# room_sensor.net
KiCad netlist of a schematic drawn in EAGLE
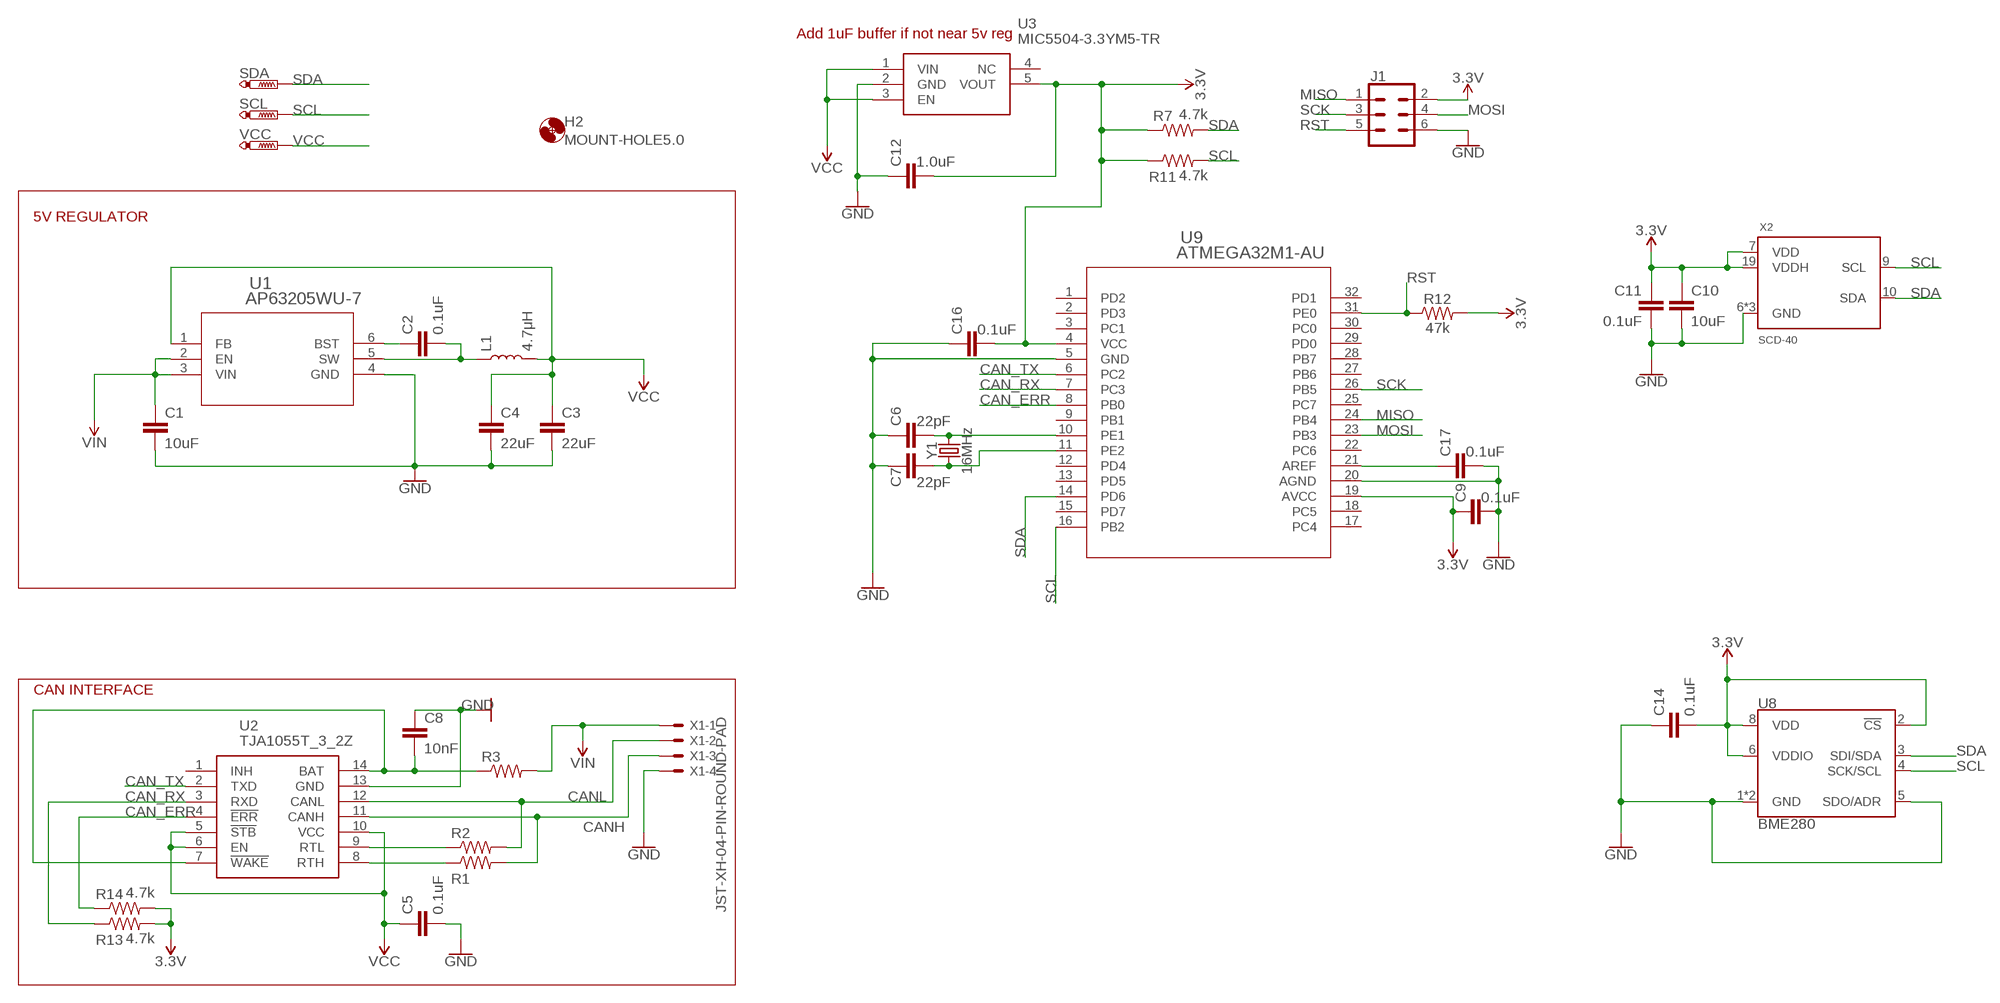
[diagram p0: schematic, sheet 1]

(export (version "E")
  (design (tool "Eeschema 10.0.6"))
  (components
    (comp (ref "C1")
      (value "10uF")
      (footprint "eagle-import:1210")
      (libsource (lib "eagle-import") (part "10UF-1210-50V-20%"))
    )
    (comp (ref "C2")
      (value "0.1uF")
      (footprint "eagle-import:0603")
      (libsource (lib "eagle-import") (part "0.1UF-0603-25V-5%"))
    )
    (comp (ref "C3")
      (value "22uF")
      (footprint "eagle-import:0805")
      (libsource (lib "eagle-import") (part "22UF-0805-6.3V-20%"))
    )
    (comp (ref "C4")
      (value "22uF")
      (footprint "eagle-import:0805")
      (libsource (lib "eagle-import") (part "22UF-0805-6.3V-20%"))
    )
    (comp (ref "C5")
      (value "0.1uF")
      (footprint "eagle-import:0603")
      (libsource (lib "eagle-import") (part "0.1UF-0603-25V-5%"))
    )
    (comp (ref "C6")
      (value "22pF")
      (footprint "eagle-import:0603")
      (libsource (lib "eagle-import") (part "22PF-0603-50V-5%"))
    )
    (comp (ref "C7")
      (value "22pF")
      (footprint "eagle-import:0603")
      (libsource (lib "eagle-import") (part "22PF-0603-50V-5%"))
    )
    (comp (ref "C8")
      (value "10nF")
      (footprint "eagle-import:0603")
      (libsource (lib "eagle-import") (part "10NF-0603-50V-10%"))
    )
    (comp (ref "C9")
      (value "0.1uF")
      (footprint "eagle-import:0603")
      (libsource (lib "eagle-import") (part "0.1UF-0603-25V-5%"))
    )
    (comp (ref "C10")
      (value "10uF")
      (footprint "eagle-import:1210")
      (libsource (lib "eagle-import") (part "10UF-1210-50V-20%"))
    )
    (comp (ref "C11")
      (value "0.1uF")
      (footprint "eagle-import:0603")
      (libsource (lib "eagle-import") (part "0.1UF-0603-25V-5%"))
    )
    (comp (ref "C12")
      (value "1.0uF")
      (footprint "eagle-import:0603")
      (libsource (lib "eagle-import") (part "1.0UF-0603-16V-10%"))
    )
    (comp (ref "C14")
      (value "0.1uF")
      (footprint "eagle-import:0603")
      (libsource (lib "eagle-import") (part "0.1UF-0603-25V-5%"))
    )
    (comp (ref "C16")
      (value "0.1uF")
      (footprint "eagle-import:0603")
      (libsource (lib "eagle-import") (part "0.1UF-0603-25V-5%"))
    )
    (comp (ref "C17")
      (value "0.1uF")
      (footprint "eagle-import:0603")
      (libsource (lib "eagle-import") (part "0.1UF-0603-25V-5%"))
    )
    (comp (ref "H2")
      (value "MOUNT-HOLE5.0")
      (footprint "eagle-import:5,0")
      (libsource (lib "eagle-import") (part "MOUNT-HOLE5.0"))
    )
    (comp (ref "J1")
      (value "CONN_03X2NO_SILK")
      (footprint "eagle-import:2X3-NS")
      (libsource (lib "eagle-import") (part "CONN_03X2NO_SILK"))
    )
    (comp (ref "L1")
      (value "4.7μH")
      (footprint "eagle-import:INDUCTOR_4X4MM")
      (libsource (lib "eagle-import") (part "4.7μH_SHIELDED_INDUCTORNPIS_LS"))
    )
    (comp (ref "R1")
      (value "RESISTOR0603")
      (footprint "eagle-import:0603")
      (libsource (lib "eagle-import") (part "RESISTOR0603"))
    )
    (comp (ref "R2")
      (value "RESISTOR0603")
      (footprint "eagle-import:0603")
      (libsource (lib "eagle-import") (part "RESISTOR0603"))
    )
    (comp (ref "R3")
      (value "RESISTOR0603")
      (footprint "eagle-import:0603")
      (libsource (lib "eagle-import") (part "RESISTOR0603"))
    )
    (comp (ref "R7")
      (value "4.7k")
      (footprint "eagle-import:0603")
      (libsource (lib "eagle-import") (part "4.7KOHM-0603-1/10W-1%"))
    )
    (comp (ref "R11")
      (value "4.7k")
      (footprint "eagle-import:0603")
      (libsource (lib "eagle-import") (part "4.7KOHM-0603-1/10W-1%"))
    )
    (comp (ref "R12")
      (value "47k")
      (footprint "eagle-import:0603")
      (libsource (lib "eagle-import") (part "47KOHM-0603-1/10W-1%"))
    )
    (comp (ref "R13")
      (value "4.7k")
      (footprint "eagle-import:0603")
      (libsource (lib "eagle-import") (part "4.7KOHM-0603-1/10W-1%"))
    )
    (comp (ref "R14")
      (value "4.7k")
      (footprint "eagle-import:0603")
      (libsource (lib "eagle-import") (part "4.7KOHM-0603-1/10W-1%"))
    )
    (comp (ref "SCL")
      (value "PTR1B1,27")
      (footprint "eagle-import:B1,27")
      (libsource (lib "eagle-import") (part "PTR1B1,27"))
    )
    (comp (ref "SDA")
      (value "PTR1B1,27")
      (footprint "eagle-import:B1,27")
      (libsource (lib "eagle-import") (part "PTR1B1,27"))
    )
    (comp (ref "U1")
      (value "AP63205WU-7")
      (footprint "eagle-import:SOIC_05WU-7_DIO")
      (fields (field (name "COPYRIGHT") "Copyright (C) 2023 Ultra Librarian. All rights reserved."))
      (libsource (lib "eagle-import") (part "AP63205WU-7"))
    )
    (comp (ref "U2")
      (value "TJA1055T_3_2Z")
      (footprint "eagle-import:SOIC127P600X175-14N")
      (fields
        (field (name "MANUFACTURER_PART_NUMBER") "TJA1055T/3/2Z")
        (field (name "MOUSER_PART_NUMBER") "771-TJA1055T/3/2Z")
      )
      (libsource (lib "eagle-import") (part "TJA1055T_3_2Z"))
    )
    (comp (ref "U3")
      (value "MIC5504-3.3YM5-TR")
      (footprint "eagle-import:SOT95P280X145-5N")
      (fields (field (name "MOUSER_PART_NUMBER") "998-MIC5504-3.3YM5TR"))
      (libsource (lib "eagle-import") (part "MIC5504-3.3YM5-TR"))
    )
    (comp (ref "U8")
      (value "BME280")
      (footprint "eagle-import:LGA-8-2.5X2.5")
      (libsource (lib "eagle-import") (part "BME280"))
    )
    (comp (ref "U9")
      (value "ATMEGA32M1-AU")
      (footprint "eagle-import:32A_ATM")
      (fields (field (name "COPYRIGHT") "Copyright (C) 2023 Ultra Librarian. All rights reserved."))
      (libsource (lib "eagle-import") (part "ATMEGA32M1-AU"))
    )
    (comp (ref "VCC")
      (value "PTR1B1,27")
      (footprint "eagle-import:B1,27")
      (libsource (lib "eagle-import") (part "PTR1B1,27"))
    )
    (comp (ref "X1")
      (value "JST-XH-04-PIN-ROUND-PAD")
      (footprint "eagle-import:JST-XH-04-PACKAGE-ROUND-PAD")
      (libsource (lib "eagle-import") (part "JST-XH-04-PIN-ROUND-PAD"))
    )
    (comp (ref "X2")
      (value "SCD-40")
      (footprint "eagle-import:SCD40")
      (libsource (lib "eagle-import") (part "SCD-40"))
    )
    (comp (ref "Y1")
      (value "16MHz")
      (footprint "eagle-import:CRYSTAL-SMD-5X3.2-4PAD")
      (libsource (lib "eagle-import") (part "CRYSTAL-16MHZSMD-5X3.2"))
    )
  )
  (nets
    (net (code "1") (name "/CANH") (class "Default")
      (node (ref "R1") (pin "2") (pinfunction "2_2") (pintype "passive"))
      (node (ref "U2") (pin "11") (pinfunction "CANH_11") (pintype "bidirectional"))
      (node (ref "X1") (pin "3") (pinfunction "S_3") (pintype "passive"))
    )
    (net (code "2") (name "/CANL") (class "Default")
      (node (ref "R2") (pin "2") (pinfunction "2_2") (pintype "passive"))
      (node (ref "U2") (pin "12") (pinfunction "CANL_12") (pintype "bidirectional"))
      (node (ref "X1") (pin "2") (pinfunction "S_2") (pintype "passive"))
    )
    (net (code "3") (name "/CAN_ERR") (class "Default")
      (node (ref "R14") (pin "1") (pinfunction "1_1") (pintype "passive"))
      (node (ref "U2") (pin "4") (pinfunction "~{ERR}_4") (pintype "bidirectional"))
      (node (ref "U9") (pin "8") (pinfunction "PB0_8") (pintype "bidirectional"))
    )
    (net (code "4") (name "/CAN_RX") (class "Default")
      (node (ref "R13") (pin "1") (pinfunction "1_1") (pintype "passive"))
      (node (ref "U2") (pin "3") (pinfunction "RXD_3") (pintype "bidirectional"))
      (node (ref "U9") (pin "7") (pinfunction "PC3_7") (pintype "bidirectional"))
    )
    (net (code "5") (name "/CAN_TX") (class "Default")
      (node (ref "U2") (pin "2") (pinfunction "TXD_2") (pintype "bidirectional"))
      (node (ref "U9") (pin "6") (pinfunction "PC2_6") (pintype "bidirectional"))
    )
    (net (code "6") (name "/MISO") (class "Default")
      (node (ref "J1") (pin "1") (pinfunction "1_1") (pintype "bidirectional"))
      (node (ref "U9") (pin "24") (pinfunction "PB4_24") (pintype "bidirectional"))
    )
    (net (code "7") (name "/MOSI") (class "Default")
      (node (ref "J1") (pin "4") (pinfunction "4_4") (pintype "bidirectional"))
      (node (ref "U9") (pin "23") (pinfunction "PB3_23") (pintype "bidirectional"))
    )
    (net (code "8") (name "/RST") (class "Default")
      (node (ref "J1") (pin "5") (pinfunction "5_5") (pintype "bidirectional"))
      (node (ref "R12") (pin "1") (pinfunction "1_1") (pintype "passive"))
      (node (ref "U9") (pin "31") (pinfunction "PE0_31") (pintype "bidirectional"))
    )
    (net (code "9") (name "/SCK") (class "Default")
      (node (ref "J1") (pin "3") (pinfunction "3_3") (pintype "bidirectional"))
      (node (ref "U9") (pin "26") (pinfunction "PB5_26") (pintype "bidirectional"))
    )
    (net (code "10") (name "/SCL") (class "Default")
      (node (ref "R11") (pin "2") (pinfunction "2_2") (pintype "passive"))
      (node (ref "SCL") (pin "TP") (pinfunction "TP_TP") (pintype "input"))
      (node (ref "U8") (pin "4") (pinfunction "SCK/SCL_4") (pintype "bidirectional"))
      (node (ref "U9") (pin "16") (pinfunction "PB2_16") (pintype "bidirectional"))
      (node (ref "X2") (pin "9") (pinfunction "SCL_9") (pintype "input"))
    )
    (net (code "11") (name "/SDA") (class "Default")
      (node (ref "R7") (pin "2") (pinfunction "2_2") (pintype "passive"))
      (node (ref "SDA") (pin "TP") (pinfunction "TP_TP") (pintype "input"))
      (node (ref "U8") (pin "3") (pinfunction "SDI/SDA_3") (pintype "bidirectional"))
      (node (ref "U9") (pin "14") (pinfunction "PD6_14") (pintype "bidirectional"))
      (node (ref "X2") (pin "10") (pinfunction "SDA_10") (pintype "bidirectional"))
    )
    (net (code "12") (name "3.3V") (class "Default")
      (node (ref "C10") (pin "1") (pinfunction "1_1") (pintype "passive"))
      (node (ref "C11") (pin "2") (pinfunction "2_2") (pintype "passive"))
      (node (ref "C12") (pin "2") (pinfunction "2_2") (pintype "passive"))
      (node (ref "C14") (pin "2") (pinfunction "2_2") (pintype "passive"))
      (node (ref "C16") (pin "2") (pinfunction "2_2") (pintype "passive"))
      (node (ref "C9") (pin "1") (pinfunction "1_1") (pintype "passive"))
      (node (ref "J1") (pin "2") (pinfunction "2_2") (pintype "bidirectional"))
      (node (ref "R11") (pin "1") (pinfunction "1_1") (pintype "passive"))
      (node (ref "R12") (pin "2") (pinfunction "2_2") (pintype "passive"))
      (node (ref "R13") (pin "2") (pinfunction "2_2") (pintype "passive"))
      (node (ref "R14") (pin "2") (pinfunction "2_2") (pintype "passive"))
      (node (ref "R7") (pin "1") (pinfunction "1_1") (pintype "passive"))
      (node (ref "U3") (pin "5") (pinfunction "VOUT_5") (pintype "bidirectional"))
      (node (ref "U8") (pin "2") (pinfunction "~{CS}_2") (pintype "bidirectional"))
      (node (ref "U8") (pin "6") (pinfunction "VDDIO_6") (pintype "bidirectional"))
      (node (ref "U8") (pin "8") (pinfunction "VDD_8") (pintype "bidirectional"))
      (node (ref "U9") (pin "19") (pinfunction "AVCC_19") (pintype "power_in"))
      (node (ref "U9") (pin "4") (pinfunction "VCC_4") (pintype "power_in"))
      (node (ref "X2") (pin "19") (pinfunction "VDDH_19") (pintype "power_in"))
      (node (ref "X2") (pin "7") (pinfunction "VDD_7") (pintype "power_in"))
    )
    (net (code "13") (name "GND") (class "Default")
      (node (ref "C1") (pin "2") (pinfunction "2_2") (pintype "passive"))
      (node (ref "C10") (pin "2") (pinfunction "2_2") (pintype "passive"))
      (node (ref "C11") (pin "1") (pinfunction "1_1") (pintype "passive"))
      (node (ref "C12") (pin "1") (pinfunction "1_1") (pintype "passive"))
      (node (ref "C14") (pin "1") (pinfunction "1_1") (pintype "passive"))
      (node (ref "C16") (pin "1") (pinfunction "1_1") (pintype "passive"))
      (node (ref "C17") (pin "2") (pinfunction "2_2") (pintype "passive"))
      (node (ref "C3") (pin "2") (pinfunction "2_2") (pintype "passive"))
      (node (ref "C4") (pin "2") (pinfunction "2_2") (pintype "passive"))
      (node (ref "C5") (pin "2") (pinfunction "2_2") (pintype "passive"))
      (node (ref "C6") (pin "1") (pinfunction "1_1") (pintype "passive"))
      (node (ref "C7") (pin "1") (pinfunction "1_1") (pintype "passive"))
      (node (ref "C8") (pin "1") (pinfunction "1_1") (pintype "passive"))
      (node (ref "C9") (pin "2") (pinfunction "2_2") (pintype "passive"))
      (node (ref "J1") (pin "6") (pinfunction "6_6") (pintype "bidirectional"))
      (node (ref "U1") (pin "4") (pinfunction "GND_4") (pintype "passive"))
      (node (ref "U2") (pin "13") (pinfunction "GND_13") (pintype "bidirectional"))
      (node (ref "U3") (pin "2") (pinfunction "GND_2") (pintype "bidirectional"))
      (node (ref "U8") (pin "1") (pinfunction "GND_1") (pintype "bidirectional"))
      (node (ref "U8") (pin "5") (pinfunction "SDO/ADR_5") (pintype "bidirectional"))
      (node (ref "U8") (pin "7") (pinfunction "GND_7") (pintype "bidirectional"))
      (node (ref "U9") (pin "20") (pinfunction "AGND_20") (pintype "power_in"))
      (node (ref "U9") (pin "5") (pinfunction "GND_5") (pintype "power_in"))
      (node (ref "X1") (pin "4") (pinfunction "S_4") (pintype "passive"))
      (node (ref "X2") (pin "20") (pinfunction "GND_20") (pintype "power_in"))
      (node (ref "X2") (pin "6") (pinfunction "GND_6") (pintype "power_in"))
      (node (ref "X2") (pin "P$1") (pinfunction "GND_P$1") (pintype "power_in"))
    )
    (net (code "14") (name "Net-(L1-1)") (class "Default")
      (node (ref "C2") (pin "2") (pinfunction "2_2") (pintype "passive"))
      (node (ref "L1") (pin "P$1") (pinfunction "1_P$1") (pintype "passive"))
      (node (ref "U1") (pin "5") (pinfunction "SW_5") (pintype "passive"))
    )
    (net (code "15") (name "Net-(U1-BST)") (class "Default")
      (node (ref "C2") (pin "1") (pinfunction "1_1") (pintype "passive"))
      (node (ref "U1") (pin "6") (pinfunction "BST_6") (pintype "passive"))
    )
    (net (code "16") (name "Net-(U2-BAT)") (class "Default")
      (node (ref "C8") (pin "2") (pinfunction "2_2") (pintype "passive"))
      (node (ref "R3") (pin "1") (pinfunction "1_1") (pintype "passive"))
      (node (ref "U2") (pin "14") (pinfunction "BAT_14") (pintype "bidirectional"))
      (node (ref "U2") (pin "7") (pinfunction "~{WAKE}_7") (pintype "bidirectional"))
    )
    (net (code "17") (name "Net-(U2-RTH)") (class "Default")
      (node (ref "R1") (pin "1") (pinfunction "1_1") (pintype "passive"))
      (node (ref "U2") (pin "8") (pinfunction "RTH_8") (pintype "bidirectional"))
    )
    (net (code "18") (name "Net-(U2-RTL)") (class "Default")
      (node (ref "R2") (pin "1") (pinfunction "1_1") (pintype "passive"))
      (node (ref "U2") (pin "9") (pinfunction "RTL_9") (pintype "bidirectional"))
    )
    (net (code "19") (name "Net-(U9-AREF)") (class "Default")
      (node (ref "C17") (pin "1") (pinfunction "1_1") (pintype "passive"))
      (node (ref "U9") (pin "21") (pinfunction "AREF_21") (pintype "passive"))
    )
    (net (code "20") (name "Net-(U9-PE1)") (class "Default")
      (node (ref "C6") (pin "2") (pinfunction "2_2") (pintype "passive"))
      (node (ref "U9") (pin "10") (pinfunction "PE1_10") (pintype "bidirectional"))
      (node (ref "Y1") (pin "3") (pinfunction "2_3") (pintype "passive"))
    )
    (net (code "21") (name "Net-(U9-PE2)") (class "Default")
      (node (ref "C7") (pin "2") (pinfunction "2_2") (pintype "passive"))
      (node (ref "U9") (pin "11") (pinfunction "PE2_11") (pintype "bidirectional"))
      (node (ref "Y1") (pin "1") (pinfunction "1_1") (pintype "passive"))
    )
    (net (code "22") (name "VCC") (class "Default")
      (node (ref "C3") (pin "1") (pinfunction "1_1") (pintype "passive"))
      (node (ref "C4") (pin "1") (pinfunction "1_1") (pintype "passive"))
      (node (ref "C5") (pin "1") (pinfunction "1_1") (pintype "passive"))
      (node (ref "L1") (pin "P$2") (pinfunction "2_P$2") (pintype "passive"))
      (node (ref "U1") (pin "1") (pinfunction "FB_1") (pintype "passive"))
      (node (ref "U2") (pin "10") (pinfunction "VCC_10") (pintype "bidirectional"))
      (node (ref "U2") (pin "5") (pinfunction "~{STB}_5") (pintype "bidirectional"))
      (node (ref "U2") (pin "6") (pinfunction "EN_6") (pintype "bidirectional"))
      (node (ref "U3") (pin "1") (pinfunction "VIN_1") (pintype "bidirectional"))
      (node (ref "U3") (pin "3") (pinfunction "EN_3") (pintype "bidirectional"))
      (node (ref "VCC") (pin "TP") (pinfunction "TP_TP") (pintype "input"))
    )
    (net (code "23") (name "VIN") (class "Default")
      (node (ref "C1") (pin "1") (pinfunction "1_1") (pintype "passive"))
      (node (ref "R3") (pin "2") (pinfunction "2_2") (pintype "passive"))
      (node (ref "U1") (pin "2") (pinfunction "EN_2") (pintype "passive"))
      (node (ref "U1") (pin "3") (pinfunction "VIN_3") (pintype "passive"))
      (node (ref "X1") (pin "1") (pinfunction "S_1") (pintype "passive"))
    )
    (net (code "24") (name "unconnected-(U2-INH-Pad1)") (class "Default")
      (node (ref "U2") (pin "1") (pinfunction "INH_1") (pintype "bidirectional"))
    )
    (net (code "25") (name "unconnected-(U3-NC-Pad4)") (class "Default")
      (node (ref "U3") (pin "4") (pinfunction "NC_4") (pintype "no_connect"))
    )
    (net (code "26") (name "unconnected-(U9-PB1-Pad9)") (class "Default")
      (node (ref "U9") (pin "9") (pinfunction "PB1_9") (pintype "bidirectional"))
    )
    (net (code "27") (name "unconnected-(U9-PB6-Pad27)") (class "Default")
      (node (ref "U9") (pin "27") (pinfunction "PB6_27") (pintype "bidirectional"))
    )
    (net (code "28") (name "unconnected-(U9-PB7-Pad28)") (class "Default")
      (node (ref "U9") (pin "28") (pinfunction "PB7_28") (pintype "bidirectional"))
    )
    (net (code "29") (name "unconnected-(U9-PC0-Pad30)") (class "Default")
      (node (ref "U9") (pin "30") (pinfunction "PC0_30") (pintype "bidirectional"))
    )
    (net (code "30") (name "unconnected-(U9-PC1-Pad3)") (class "Default")
      (node (ref "U9") (pin "3") (pinfunction "PC1_3") (pintype "bidirectional"))
    )
    (net (code "31") (name "unconnected-(U9-PC4-Pad17)") (class "Default")
      (node (ref "U9") (pin "17") (pinfunction "PC4_17") (pintype "bidirectional"))
    )
    (net (code "32") (name "unconnected-(U9-PC5-Pad18)") (class "Default")
      (node (ref "U9") (pin "18") (pinfunction "PC5_18") (pintype "bidirectional"))
    )
    (net (code "33") (name "unconnected-(U9-PC6-Pad22)") (class "Default")
      (node (ref "U9") (pin "22") (pinfunction "PC6_22") (pintype "bidirectional"))
    )
    (net (code "34") (name "unconnected-(U9-PC7-Pad25)") (class "Default")
      (node (ref "U9") (pin "25") (pinfunction "PC7_25") (pintype "bidirectional"))
    )
    (net (code "35") (name "unconnected-(U9-PD0-Pad29)") (class "Default")
      (node (ref "U9") (pin "29") (pinfunction "PD0_29") (pintype "bidirectional"))
    )
    (net (code "36") (name "unconnected-(U9-PD1-Pad32)") (class "Default")
      (node (ref "U9") (pin "32") (pinfunction "PD1_32") (pintype "bidirectional"))
    )
    (net (code "37") (name "unconnected-(U9-PD2-Pad1)") (class "Default")
      (node (ref "U9") (pin "1") (pinfunction "PD2_1") (pintype "bidirectional"))
    )
    (net (code "38") (name "unconnected-(U9-PD3-Pad2)") (class "Default")
      (node (ref "U9") (pin "2") (pinfunction "PD3_2") (pintype "bidirectional"))
    )
    (net (code "39") (name "unconnected-(U9-PD4-Pad12)") (class "Default")
      (node (ref "U9") (pin "12") (pinfunction "PD4_12") (pintype "bidirectional"))
    )
    (net (code "40") (name "unconnected-(U9-PD5-Pad13)") (class "Default")
      (node (ref "U9") (pin "13") (pinfunction "PD5_13") (pintype "bidirectional"))
    )
    (net (code "41") (name "unconnected-(U9-PD7-Pad15)") (class "Default")
      (node (ref "U9") (pin "15") (pinfunction "PD7_15") (pintype "bidirectional"))
    )
  )
)
